# FLYTE-v2.net
KiCad netlist of a schematic drawn in EAGLE
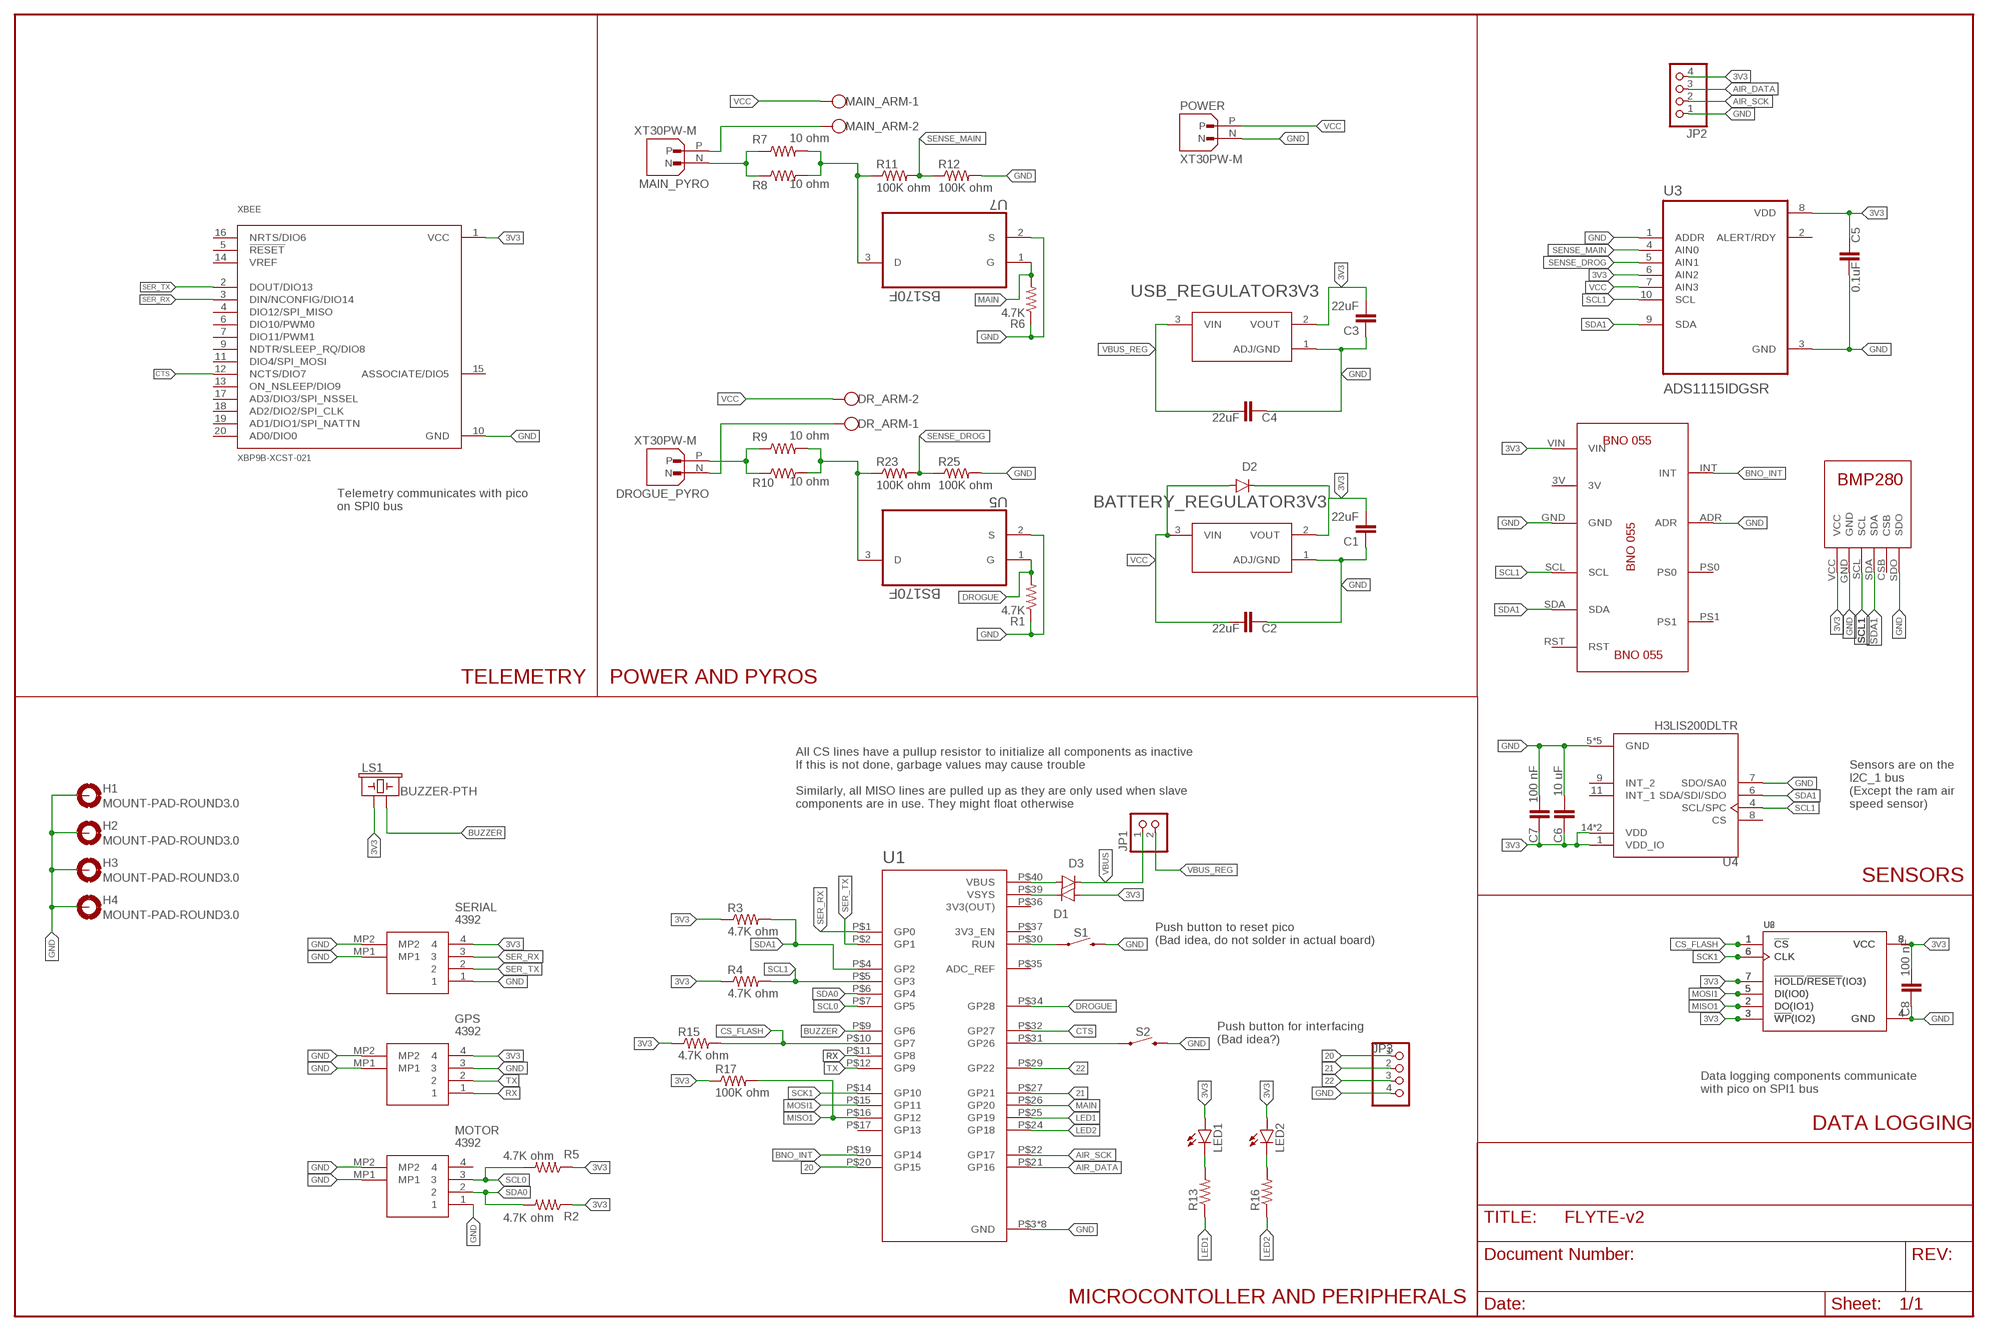
[diagram p0: schematic, sheet 1]

(export (version "E")
  (design (tool "Eeschema 10.0.6"))
  (components
    (comp (ref "BATTERY_REGULATOR3V3")
      (value "AMS1117-3.3")
      (footprint "eagle-import:SOT229P700X180-4N")
      (fields (field (name "MF") "Advanced Monolithic Systems"))
      (libsource (lib "eagle-import") (part "AMS1117-3.3"))
    )
    (comp (ref "C1")
      (value "22uF")
      (footprint "eagle-import:0805")
      (libsource (lib "eagle-import") (part "22UF-0805-6.3V-20%"))
    )
    (comp (ref "C2")
      (value "22uF")
      (footprint "eagle-import:0805")
      (libsource (lib "eagle-import") (part "22UF-0805-6.3V-20%"))
    )
    (comp (ref "C3")
      (value "22uF")
      (footprint "eagle-import:0805")
      (libsource (lib "eagle-import") (part "22UF-0805-6.3V-20%"))
    )
    (comp (ref "C4")
      (value "22uF")
      (footprint "eagle-import:0805")
      (libsource (lib "eagle-import") (part "22UF-0805-6.3V-20%"))
    )
    (comp (ref "C5")
      (value "0.1uF")
      (footprint "eagle-import:0805")
      (libsource (lib "eagle-import") (part "22UF-0805-6.3V-20%"))
    )
    (comp (ref "C6")
      (value "10 uF")
      (footprint "eagle-import:0805")
      (libsource (lib "eagle-import") (part "22UF-0805-6.3V-20%"))
    )
    (comp (ref "C7")
      (value "100 nF")
      (footprint "eagle-import:0805")
      (libsource (lib "eagle-import") (part "22UF-0805-6.3V-20%"))
    )
    (comp (ref "C8")
      (value "100 nF")
      (footprint "eagle-import:0805")
      (libsource (lib "eagle-import") (part "22UF-0805-6.3V-20%"))
    )
    (comp (ref "D1")
      (value "1N4004")
      (footprint "eagle-import:DO41-10")
      (libsource (lib "eagle-import") (part "1N4004"))
    )
    (comp (ref "D2")
      (value "1N4004")
      (footprint "eagle-import:DO41-10")
      (libsource (lib "eagle-import") (part "1N4004"))
    )
    (comp (ref "D3")
      (value "1N4004")
      (footprint "eagle-import:DO41-10")
      (libsource (lib "eagle-import") (part "1N4004"))
    )
    (comp (ref "DROGUE_PYRO")
      (value "XT30PW-M")
      (footprint "eagle-import:AMASS_XT30PW-M")
      (fields (field (name "MF") "AMASS"))
      (libsource (lib "eagle-import") (part "XT30PW-M"))
    )
    (comp (ref "DR_ARM")
      (value "W237-102")
      (footprint "eagle-import:W237-102")
      (fields (field (name "MPN") "237-102"))
      (libsource (lib "eagle-import") (part "W237-102"))
    )
    (comp (ref "GPS")
      (value "4392")
      (footprint "eagle-import:4392")
      (fields (field (name "MOUSER_PART_NUMBER") "485-4392"))
      (libsource (lib "eagle-import") (part "4392"))
    )
    (comp (ref "H1")
      (value "MOUNT-PAD-ROUND3.0")
      (footprint "eagle-import:3,0-PAD")
      (libsource (lib "eagle-import") (part "MOUNT-PAD-ROUND3.0"))
    )
    (comp (ref "H2")
      (value "MOUNT-PAD-ROUND3.0")
      (footprint "eagle-import:3,0-PAD")
      (libsource (lib "eagle-import") (part "MOUNT-PAD-ROUND3.0"))
    )
    (comp (ref "H3")
      (value "MOUNT-PAD-ROUND3.0")
      (footprint "eagle-import:3,0-PAD")
      (libsource (lib "eagle-import") (part "MOUNT-PAD-ROUND3.0"))
    )
    (comp (ref "H4")
      (value "MOUNT-PAD-ROUND3.0")
      (footprint "eagle-import:3,0-PAD")
      (libsource (lib "eagle-import") (part "MOUNT-PAD-ROUND3.0"))
    )
    (comp (ref "JP1")
      (value "PINHD-1X2")
      (footprint "eagle-import:1X02")
      (libsource (lib "eagle-import") (part "PINHD-1X2"))
    )
    (comp (ref "JP2")
      (value "PINHD-1X4")
      (footprint "eagle-import:1X04")
      (libsource (lib "eagle-import") (part "PINHD-1X4"))
    )
    (comp (ref "JP3")
      (value "PINHD-1X4")
      (footprint "eagle-import:1X04")
      (libsource (lib "eagle-import") (part "PINHD-1X4"))
    )
    (comp (ref "LED1")
      (value "LEDCHIPLED_1206")
      (footprint "eagle-import:CHIPLED_1206")
      (libsource (lib "eagle-import") (part "LEDCHIPLED_1206"))
    )
    (comp (ref "LED2")
      (value "LEDCHIPLED_1206")
      (footprint "eagle-import:CHIPLED_1206")
      (libsource (lib "eagle-import") (part "LEDCHIPLED_1206"))
    )
    (comp (ref "LS1")
      (value "BUZZER-PTH")
      (footprint "eagle-import:BUZZER-12MM")
      (libsource (lib "eagle-import") (part "BUZZER-PTH"))
    )
    (comp (ref "MAIN_ARM")
      (value "W237-102")
      (footprint "eagle-import:W237-102")
      (fields (field (name "MPN") "237-102"))
      (libsource (lib "eagle-import") (part "W237-102"))
    )
    (comp (ref "MAIN_PYRO")
      (value "XT30PW-M")
      (footprint "eagle-import:AMASS_XT30PW-M")
      (fields (field (name "MF") "AMASS"))
      (libsource (lib "eagle-import") (part "XT30PW-M"))
    )
    (comp (ref "MOTOR")
      (value "4392")
      (footprint "eagle-import:4392")
      (fields (field (name "MOUSER_PART_NUMBER") "485-4392"))
      (libsource (lib "eagle-import") (part "4392"))
    )
    (comp (ref "POWER")
      (value "XT30PW-M")
      (footprint "eagle-import:AMASS_XT30PW-M")
      (fields (field (name "MF") "AMASS"))
      (libsource (lib "eagle-import") (part "XT30PW-M"))
    )
    (comp (ref "R1")
      (value "4.7K")
      (footprint "eagle-import:R0805")
      (libsource (lib "eagle-import") (part "R-US_R0805"))
    )
    (comp (ref "R2")
      (value "4.7K ohm")
      (footprint "eagle-import:R0805")
      (libsource (lib "eagle-import") (part "R-US_R0805"))
    )
    (comp (ref "R3")
      (value "4.7K ohm")
      (footprint "eagle-import:R0805")
      (libsource (lib "eagle-import") (part "R-US_R0805"))
    )
    (comp (ref "R4")
      (value "4.7K ohm")
      (footprint "eagle-import:R0805")
      (libsource (lib "eagle-import") (part "R-US_R0805"))
    )
    (comp (ref "R5")
      (value "4.7K ohm")
      (footprint "eagle-import:R0805")
      (libsource (lib "eagle-import") (part "R-US_R0805"))
    )
    (comp (ref "R6")
      (value "4.7K")
      (footprint "eagle-import:R0805")
      (libsource (lib "eagle-import") (part "R-US_R0805"))
    )
    (comp (ref "R7")
      (value "10 ohm")
      (footprint "eagle-import:0207_10")
      (libsource (lib "eagle-import") (part "R-US_0207/10"))
    )
    (comp (ref "R8")
      (value "10 ohm")
      (footprint "eagle-import:0207_10")
      (libsource (lib "eagle-import") (part "R-US_0207/10"))
    )
    (comp (ref "R9")
      (value "10 ohm")
      (footprint "eagle-import:0207_10")
      (libsource (lib "eagle-import") (part "R-US_0207/10"))
    )
    (comp (ref "R10")
      (value "10 ohm")
      (footprint "eagle-import:0207_10")
      (libsource (lib "eagle-import") (part "R-US_0207/10"))
    )
    (comp (ref "R11")
      (value "100K ohm")
      (footprint "eagle-import:R0805")
      (libsource (lib "eagle-import") (part "R-US_R0805"))
    )
    (comp (ref "R12")
      (value "100K ohm")
      (footprint "eagle-import:R0805")
      (libsource (lib "eagle-import") (part "R-US_R0805"))
    )
    (comp (ref "R13")
      (value "R-US_R0805")
      (footprint "eagle-import:R0805")
      (libsource (lib "eagle-import") (part "R-US_R0805"))
    )
    (comp (ref "R15")
      (value "4.7K ohm")
      (footprint "eagle-import:R0805")
      (libsource (lib "eagle-import") (part "R-US_R0805"))
    )
    (comp (ref "R16")
      (value "R-US_R0805")
      (footprint "eagle-import:R0805")
      (libsource (lib "eagle-import") (part "R-US_R0805"))
    )
    (comp (ref "R17")
      (value "100K ohm")
      (footprint "eagle-import:R0805")
      (libsource (lib "eagle-import") (part "R-US_R0805"))
    )
    (comp (ref "R23")
      (value "100K ohm")
      (footprint "eagle-import:R0805")
      (libsource (lib "eagle-import") (part "R-US_R0805"))
    )
    (comp (ref "R25")
      (value "100K ohm")
      (footprint "eagle-import:R0805")
      (libsource (lib "eagle-import") (part "R-US_R0805"))
    )
    (comp (ref "S1")
      (value "MOMENTARY-SWITCH-SPST-PTH-6.0MM")
      (footprint "eagle-import:TACTILE_SWITCH_PTH_6.0MM")
      (libsource (lib "eagle-import") (part "MOMENTARY-SWITCH-SPST-PTH-6.0MM"))
    )
    (comp (ref "S2")
      (value "MOMENTARY-SWITCH-SPST-PTH-6.0MM")
      (footprint "eagle-import:TACTILE_SWITCH_PTH_6.0MM")
      (libsource (lib "eagle-import") (part "MOMENTARY-SWITCH-SPST-PTH-6.0MM"))
    )
    (comp (ref "SERIAL")
      (value "4392")
      (footprint "eagle-import:4392")
      (fields (field (name "MOUSER_PART_NUMBER") "485-4392"))
      (libsource (lib "eagle-import") (part "4392"))
    )
    (comp (ref "U$1")
      (value "BMP280")
      (footprint "eagle-import:BMP280")
      (libsource (lib "eagle-import") (part "BMP280"))
    )
    (comp (ref "U$4")
      (value "BNO055")
      (footprint "eagle-import:BNO055")
      (libsource (lib "eagle-import") (part "BNO055"))
    )
    (comp (ref "U1")
      (value "RASPBERRY_PICO-NO_DEBUG")
      (footprint "eagle-import:PICO-PKG-NO_DEBUG")
      (libsource (lib "eagle-import") (part "RASPBERRY_PICO-NO_DEBUG"))
    )
    (comp (ref "U2")
      (value "W25Q32JVSSIQ")
      (footprint "eagle-import:SOIC127P790X216-8N")
      (fields (field (name "MF") "Winbond"))
      (libsource (lib "eagle-import") (part "W25Q32JVSSIQ"))
    )
    (comp (ref "U3")
      (value "ADS1115IDGSR")
      (footprint "eagle-import:SOP50P490X110-10N")
      (fields (field (name "MF") "Texas Instruments"))
      (libsource (lib "eagle-import") (part "ADS1115IDGSR"))
    )
    (comp (ref "U4")
      (value "H3LIS200DLTR")
      (footprint "eagle-import:PQFN50P300X300X100-16N")
      (fields (field (name "MF") "STMicroelectronics"))
      (libsource (lib "eagle-import") (part "H3LIS200DLTR"))
    )
    (comp (ref "U5")
      (value "BS170F")
      (footprint "eagle-import:SOT91P240X120-3N")
      (fields (field (name "MF") "Diodes Inc."))
      (libsource (lib "eagle-import") (part "BS170F"))
    )
    (comp (ref "U6")
      (value "W25Q32JVSSIQ")
      (footprint "eagle-import:SOIC127P790X216-8N")
      (fields (field (name "MF") "Winbond"))
      (libsource (lib "eagle-import") (part "W25Q32JVSSIQ"))
    )
    (comp (ref "U7")
      (value "BS170F")
      (footprint "eagle-import:SOT91P240X120-3N")
      (fields (field (name "MF") "Diodes Inc."))
      (libsource (lib "eagle-import") (part "BS170F"))
    )
    (comp (ref "USB_REGULATOR3V3")
      (value "AMS1117-3.3")
      (footprint "eagle-import:SOT229P700X180-4N")
      (fields (field (name "MF") "Advanced Monolithic Systems"))
      (libsource (lib "eagle-import") (part "AMS1117-3.3"))
    )
    (comp (ref "XBEE")
      (value "XBP9B-XCST-021")
      (footprint "eagle-import:DIP2200W51P200L3294H279Q20P")
      (fields (field (name "MF") "Digi International"))
      (libsource (lib "eagle-import") (part "XBP9B-XCST-021"))
    )
  )
  (nets
    (net (code "1") (name "/3V3(OUT)") (class "Default")
      (node (ref "U1") (pin "P$36") (pinfunction "3V3(OUT)_P$36") (pintype "power_in"))
    )
    (net (code "2") (name "3V3") (class "Default")
      (node (ref "BATTERY_REGULATOR3V3") (pin "2") (pinfunction "VOUT_2") (pintype "output"))
      (node (ref "C1") (pin "2") (pinfunction "2_2") (pintype "passive"))
      (node (ref "C3") (pin "2") (pinfunction "2_2") (pintype "passive"))
      (node (ref "C5") (pin "1") (pinfunction "1_1") (pintype "passive"))
      (node (ref "C6") (pin "1") (pinfunction "1_1") (pintype "passive"))
      (node (ref "C7") (pin "1") (pinfunction "1_1") (pintype "passive"))
      (node (ref "C8") (pin "2") (pinfunction "2_2") (pintype "passive"))
      (node (ref "D1") (pin "A") (pinfunction "A_A") (pintype "passive"))
      (node (ref "D2") (pin "C") (pinfunction "C_C") (pintype "passive"))
      (node (ref "GPS") (pin "4") (pinfunction "4_4") (pintype "bidirectional"))
      (node (ref "JP2") (pin "4") (pinfunction "4_4") (pintype "passive"))
      (node (ref "LED1") (pin "A") (pinfunction "A_A") (pintype "passive"))
      (node (ref "LED2") (pin "A") (pinfunction "A_A") (pintype "passive"))
      (node (ref "LS1") (pin "+") (pinfunction "1_+") (pintype "passive"))
      (node (ref "R15") (pin "1") (pinfunction "1_1") (pintype "passive"))
      (node (ref "R17") (pin "1") (pinfunction "1_1") (pintype "passive"))
      (node (ref "R2") (pin "1") (pinfunction "1_1") (pintype "passive"))
      (node (ref "R3") (pin "1") (pinfunction "1_1") (pintype "passive"))
      (node (ref "R4") (pin "1") (pinfunction "1_1") (pintype "passive"))
      (node (ref "R5") (pin "1") (pinfunction "1_1") (pintype "passive"))
      (node (ref "SERIAL") (pin "4") (pinfunction "4_4") (pintype "bidirectional"))
      (node (ref "U$1") (pin "VCC") (pinfunction "VCC_VCC") (pintype "bidirectional"))
      (node (ref "U$4") (pin "VIN") (pinfunction "VIN_VIN") (pintype "bidirectional"))
      (node (ref "U2") (pin "3") (pinfunction "~{WP}(IO2)_3") (pintype "bidirectional"))
      (node (ref "U2") (pin "7") (pinfunction "~{HOLD}/~{RESET}(IO3)_7") (pintype "bidirectional"))
      (node (ref "U2") (pin "8") (pinfunction "VCC_8") (pintype "power_in"))
      (node (ref "U3") (pin "6") (pinfunction "AIN2_6") (pintype "input"))
      (node (ref "U3") (pin "8") (pinfunction "VDD_8") (pintype "power_in"))
      (node (ref "U4") (pin "1") (pinfunction "VDD_IO_1") (pintype "power_in"))
      (node (ref "U4") (pin "14") (pinfunction "VDD_14") (pintype "power_in"))
      (node (ref "U4") (pin "15") (pinfunction "VDD_15") (pintype "power_in"))
      (node (ref "U6") (pin "3") (pinfunction "~{WP}(IO2)_3") (pintype "bidirectional"))
      (node (ref "U6") (pin "7") (pinfunction "~{HOLD}/~{RESET}(IO3)_7") (pintype "bidirectional"))
      (node (ref "U6") (pin "8") (pinfunction "VCC_8") (pintype "power_in"))
      (node (ref "USB_REGULATOR3V3") (pin "2") (pinfunction "VOUT_2") (pintype "output"))
      (node (ref "XBEE") (pin "1") (pinfunction "VCC_1") (pintype "power_in"))
    )
    (net (code "3") (name "20") (class "Default")
      (node (ref "JP3") (pin "1") (pinfunction "1_1") (pintype "passive"))
      (node (ref "U1") (pin "P$20") (pinfunction "GP15_P$20") (pintype "bidirectional"))
    )
    (net (code "4") (name "21") (class "Default")
      (node (ref "JP3") (pin "2") (pinfunction "2_2") (pintype "passive"))
      (node (ref "U1") (pin "P$27") (pinfunction "GP21_P$27") (pintype "bidirectional"))
    )
    (net (code "5") (name "22") (class "Default")
      (node (ref "JP3") (pin "3") (pinfunction "3_3") (pintype "passive"))
      (node (ref "U1") (pin "P$29") (pinfunction "GP22_P$29") (pintype "bidirectional"))
    )
    (net (code "6") (name "AIR_DATA") (class "Default")
      (node (ref "JP2") (pin "3") (pinfunction "3_3") (pintype "passive"))
      (node (ref "U1") (pin "P$21") (pinfunction "GP16_P$21") (pintype "bidirectional"))
    )
    (net (code "7") (name "AIR_SCK") (class "Default")
      (node (ref "JP2") (pin "2") (pinfunction "2_2") (pintype "passive"))
      (node (ref "U1") (pin "P$22") (pinfunction "GP17_P$22") (pintype "bidirectional"))
    )
    (net (code "8") (name "BNO_INT") (class "Default")
      (node (ref "U$4") (pin "INT") (pinfunction "INT_INT") (pintype "bidirectional"))
      (node (ref "U1") (pin "P$19") (pinfunction "GP14_P$19") (pintype "bidirectional"))
    )
    (net (code "9") (name "BUZZER") (class "Default")
      (node (ref "LS1") (pin "-") (pinfunction "2_-") (pintype "passive"))
      (node (ref "U1") (pin "P$9") (pinfunction "GP6_P$9") (pintype "bidirectional"))
    )
    (net (code "10") (name "CS_FLASH") (class "Default")
      (node (ref "R15") (pin "2") (pinfunction "2_2") (pintype "passive"))
      (node (ref "U1") (pin "P$10") (pinfunction "GP7_P$10") (pintype "bidirectional"))
      (node (ref "U2") (pin "1") (pinfunction "~{CS}_1") (pintype "input"))
      (node (ref "U6") (pin "1") (pinfunction "~{CS}_1") (pintype "input"))
    )
    (net (code "11") (name "CTS") (class "Default")
      (node (ref "U1") (pin "P$32") (pinfunction "GP27_P$32") (pintype "bidirectional"))
      (node (ref "XBEE") (pin "12") (pinfunction "NCTS/DIO7_12") (pintype "bidirectional"))
    )
    (net (code "12") (name "DROGUE") (class "Default")
      (node (ref "R1") (pin "2") (pinfunction "2_2") (pintype "passive"))
      (node (ref "U1") (pin "P$34") (pinfunction "GP28_P$34") (pintype "bidirectional"))
      (node (ref "U5") (pin "1") (pinfunction "G_1") (pintype "passive"))
    )
    (net (code "13") (name "GND") (class "Default")
      (node (ref "BATTERY_REGULATOR3V3") (pin "1") (pinfunction "ADJ/GND_1") (pintype "power_in"))
      (node (ref "C1") (pin "1") (pinfunction "1_1") (pintype "passive"))
      (node (ref "C2") (pin "1") (pinfunction "1_1") (pintype "passive"))
      (node (ref "C3") (pin "1") (pinfunction "1_1") (pintype "passive"))
      (node (ref "C4") (pin "1") (pinfunction "1_1") (pintype "passive"))
      (node (ref "C5") (pin "2") (pinfunction "2_2") (pintype "passive"))
      (node (ref "C6") (pin "2") (pinfunction "2_2") (pintype "passive"))
      (node (ref "C7") (pin "2") (pinfunction "2_2") (pintype "passive"))
      (node (ref "C8") (pin "1") (pinfunction "1_1") (pintype "passive"))
      (node (ref "GPS") (pin "3") (pinfunction "3_3") (pintype "bidirectional"))
      (node (ref "GPS") (pin "MP1") (pinfunction "MP1_MP1") (pintype "bidirectional"))
      (node (ref "GPS") (pin "MP2") (pinfunction "MP2_MP2") (pintype "bidirectional"))
      (node (ref "H1") (pin "B3,0") (pinfunction "MOUNT_B3,0") (pintype "passive"))
      (node (ref "H2") (pin "B3,0") (pinfunction "MOUNT_B3,0") (pintype "passive"))
      (node (ref "H3") (pin "B3,0") (pinfunction "MOUNT_B3,0") (pintype "passive"))
      (node (ref "H4") (pin "B3,0") (pinfunction "MOUNT_B3,0") (pintype "passive"))
      (node (ref "JP2") (pin "1") (pinfunction "1_1") (pintype "passive"))
      (node (ref "JP3") (pin "4") (pinfunction "4_4") (pintype "passive"))
      (node (ref "MOTOR") (pin "1") (pinfunction "1_1") (pintype "bidirectional"))
      (node (ref "MOTOR") (pin "MP1") (pinfunction "MP1_MP1") (pintype "bidirectional"))
      (node (ref "MOTOR") (pin "MP2") (pinfunction "MP2_MP2") (pintype "bidirectional"))
      (node (ref "POWER") (pin "N") (pinfunction "N_N") (pintype "power_in"))
      (node (ref "R1") (pin "1") (pinfunction "1_1") (pintype "passive"))
      (node (ref "R12") (pin "2") (pinfunction "2_2") (pintype "passive"))
      (node (ref "R25") (pin "2") (pinfunction "2_2") (pintype "passive"))
      (node (ref "R6") (pin "1") (pinfunction "1_1") (pintype "passive"))
      (node (ref "S1") (pin "3") (pinfunction "2_3") (pintype "passive"))
      (node (ref "S2") (pin "3") (pinfunction "2_3") (pintype "passive"))
      (node (ref "SERIAL") (pin "1") (pinfunction "1_1") (pintype "bidirectional"))
      (node (ref "SERIAL") (pin "MP1") (pinfunction "MP1_MP1") (pintype "bidirectional"))
      (node (ref "SERIAL") (pin "MP2") (pinfunction "MP2_MP2") (pintype "bidirectional"))
      (node (ref "U$1") (pin "GND") (pinfunction "GND_GND") (pintype "bidirectional"))
      (node (ref "U$1") (pin "SDO") (pinfunction "SDO_SDO") (pintype "bidirectional"))
      (node (ref "U$4") (pin "ADR") (pinfunction "ADR_ADR") (pintype "bidirectional"))
      (node (ref "U$4") (pin "GND") (pinfunction "GND_GND") (pintype "bidirectional"))
      (node (ref "U1") (pin "P$13") (pinfunction "GND_P$13") (pintype "power_in"))
      (node (ref "U1") (pin "P$18") (pinfunction "GND_P$18") (pintype "power_in"))
      (node (ref "U1") (pin "P$23") (pinfunction "GND_P$23") (pintype "power_in"))
      (node (ref "U1") (pin "P$28") (pinfunction "GND_P$28") (pintype "power_in"))
      (node (ref "U1") (pin "P$3") (pinfunction "GND_P$3") (pintype "power_in"))
      (node (ref "U1") (pin "P$33") (pinfunction "GND_P$33") (pintype "power_in"))
      (node (ref "U1") (pin "P$38") (pinfunction "GND_P$38") (pintype "power_in"))
      (node (ref "U1") (pin "P$8") (pinfunction "GND_P$8") (pintype "power_in"))
      (node (ref "U2") (pin "4") (pinfunction "GND_4") (pintype "power_in"))
      (node (ref "U3") (pin "1") (pinfunction "ADDR_1") (pintype "input"))
      (node (ref "U3") (pin "3") (pinfunction "GND_3") (pintype "power_in"))
      (node (ref "U4") (pin "10") (pinfunction "GND_10") (pintype "power_in"))
      (node (ref "U4") (pin "12") (pinfunction "GND_12") (pintype "power_in"))
      (node (ref "U4") (pin "13") (pinfunction "GND_13") (pintype "power_in"))
      (node (ref "U4") (pin "16") (pinfunction "GND_16") (pintype "power_in"))
      (node (ref "U4") (pin "5") (pinfunction "GND_5") (pintype "power_in"))
      (node (ref "U4") (pin "7") (pinfunction "SDO/SA0_7") (pintype "output"))
      (node (ref "U5") (pin "2") (pinfunction "S_2") (pintype "passive"))
      (node (ref "U6") (pin "4") (pinfunction "GND_4") (pintype "power_in"))
      (node (ref "U7") (pin "2") (pinfunction "S_2") (pintype "passive"))
      (node (ref "USB_REGULATOR3V3") (pin "1") (pinfunction "ADJ/GND_1") (pintype "power_in"))
      (node (ref "XBEE") (pin "10") (pinfunction "GND_10") (pintype "power_in"))
    )
    (net (code "14") (name "LED1") (class "Default")
      (node (ref "R13") (pin "1") (pinfunction "1_1") (pintype "passive"))
      (node (ref "U1") (pin "P$25") (pinfunction "GP19_P$25") (pintype "bidirectional"))
    )
    (net (code "15") (name "LED2") (class "Default")
      (node (ref "R16") (pin "1") (pinfunction "1_1") (pintype "passive"))
      (node (ref "U1") (pin "P$24") (pinfunction "GP18_P$24") (pintype "bidirectional"))
    )
    (net (code "16") (name "MAIN") (class "Default")
      (node (ref "R6") (pin "2") (pinfunction "2_2") (pintype "passive"))
      (node (ref "U1") (pin "P$26") (pinfunction "GP20_P$26") (pintype "bidirectional"))
      (node (ref "U7") (pin "1") (pinfunction "G_1") (pintype "passive"))
    )
    (net (code "17") (name "MISO1") (class "Default")
      (node (ref "R17") (pin "2") (pinfunction "2_2") (pintype "passive"))
      (node (ref "U1") (pin "P$16") (pinfunction "GP12_P$16") (pintype "bidirectional"))
      (node (ref "U2") (pin "2") (pinfunction "DO(IO1)_2") (pintype "bidirectional"))
      (node (ref "U6") (pin "2") (pinfunction "DO(IO1)_2") (pintype "bidirectional"))
    )
    (net (code "18") (name "MOSI1") (class "Default")
      (node (ref "U1") (pin "P$15") (pinfunction "GP11_P$15") (pintype "bidirectional"))
      (node (ref "U2") (pin "5") (pinfunction "DI(IO0)_5") (pintype "bidirectional"))
      (node (ref "U6") (pin "5") (pinfunction "DI(IO0)_5") (pintype "bidirectional"))
    )
    (net (code "19") (name "Net-(DROGUE_PYRO-PadP)") (class "Default")
      (node (ref "DROGUE_PYRO") (pin "P") (pinfunction "P_P") (pintype "power_in"))
      (node (ref "R10") (pin "1") (pinfunction "1_1") (pintype "passive"))
      (node (ref "R9") (pin "1") (pinfunction "1_1") (pintype "passive"))
    )
    (net (code "20") (name "Net-(DR_ARMA-KL)") (class "Default")
      (node (ref "DROGUE_PYRO") (pin "N") (pinfunction "N_N") (pintype "power_in"))
      (node (ref "DR_ARM") (pin "1") (pinfunction "KL_1") (pintype "passive"))
    )
    (net (code "21") (name "Net-(LED1-PadC)") (class "Default")
      (node (ref "LED1") (pin "C") (pinfunction "C_C") (pintype "passive"))
      (node (ref "R13") (pin "2") (pinfunction "2_2") (pintype "passive"))
    )
    (net (code "22") (name "Net-(LED2-PadC)") (class "Default")
      (node (ref "LED2") (pin "C") (pinfunction "C_C") (pintype "passive"))
      (node (ref "R16") (pin "2") (pinfunction "2_2") (pintype "passive"))
    )
    (net (code "23") (name "Net-(MAIN_ARMB-KL)") (class "Default")
      (node (ref "MAIN_ARM") (pin "2") (pinfunction "KL_2") (pintype "passive"))
      (node (ref "MAIN_PYRO") (pin "P") (pinfunction "P_P") (pintype "power_in"))
    )
    (net (code "24") (name "Net-(MAIN_PYRO-PadN)") (class "Default")
      (node (ref "MAIN_PYRO") (pin "N") (pinfunction "N_N") (pintype "power_in"))
      (node (ref "R7") (pin "1") (pinfunction "1_1") (pintype "passive"))
      (node (ref "R8") (pin "1") (pinfunction "1_1") (pintype "passive"))
    )
    (net (code "25") (name "Net-(U1-GP26)") (class "Default")
      (node (ref "S2") (pin "1") (pinfunction "1_1") (pintype "passive"))
      (node (ref "U1") (pin "P$31") (pinfunction "GP26_P$31") (pintype "bidirectional"))
    )
    (net (code "26") (name "Net-(U1-RUN)") (class "Default")
      (node (ref "S1") (pin "1") (pinfunction "1_1") (pintype "passive"))
      (node (ref "U1") (pin "P$30") (pinfunction "RUN_P$30") (pintype "input"))
    )
    (net (code "27") (name "Net-(U1-VBUS)") (class "Default")
      (node (ref "D3") (pin "A") (pinfunction "A_A") (pintype "passive"))
      (node (ref "U1") (pin "P$40") (pinfunction "VBUS_P$40") (pintype "power_in"))
    )
    (net (code "28") (name "Net-(U1-VSYS)") (class "Default")
      (node (ref "D1") (pin "C") (pinfunction "C_C") (pintype "passive"))
      (node (ref "U1") (pin "P$39") (pinfunction "VSYS_P$39") (pintype "power_in"))
    )
    (net (code "29") (name "Net-(U5-D)") (class "Default")
      (node (ref "R10") (pin "2") (pinfunction "2_2") (pintype "passive"))
      (node (ref "R23") (pin "1") (pinfunction "1_1") (pintype "passive"))
      (node (ref "R9") (pin "2") (pinfunction "2_2") (pintype "passive"))
      (node (ref "U5") (pin "3") (pinfunction "D_3") (pintype "passive"))
    )
    (net (code "30") (name "Net-(U7-D)") (class "Default")
      (node (ref "R11") (pin "1") (pinfunction "1_1") (pintype "passive"))
      (node (ref "R7") (pin "2") (pinfunction "2_2") (pintype "passive"))
      (node (ref "R8") (pin "2") (pinfunction "2_2") (pintype "passive"))
      (node (ref "U7") (pin "3") (pinfunction "D_3") (pintype "passive"))
    )
    (net (code "31") (name "RX") (class "Default")
      (node (ref "GPS") (pin "1") (pinfunction "1_1") (pintype "bidirectional"))
      (node (ref "U1") (pin "P$11") (pinfunction "GP8_P$11") (pintype "bidirectional"))
    )
    (net (code "32") (name "SCK1") (class "Default")
      (node (ref "U1") (pin "P$14") (pinfunction "GP10_P$14") (pintype "bidirectional"))
      (node (ref "U2") (pin "6") (pinfunction "CLK_6") (pintype "input"))
      (node (ref "U6") (pin "6") (pinfunction "CLK_6") (pintype "input"))
    )
    (net (code "33") (name "SCL0") (class "Default")
      (node (ref "MOTOR") (pin "3") (pinfunction "3_3") (pintype "bidirectional"))
      (node (ref "R5") (pin "2") (pinfunction "2_2") (pintype "passive"))
      (node (ref "U1") (pin "P$7") (pinfunction "GP5_P$7") (pintype "bidirectional"))
    )
    (net (code "34") (name "SCL1") (class "Default")
      (node (ref "R4") (pin "2") (pinfunction "2_2") (pintype "passive"))
      (node (ref "U$1") (pin "SCL") (pinfunction "SCL_SCL") (pintype "bidirectional"))
      (node (ref "U$4") (pin "SCL") (pinfunction "SCL_SCL") (pintype "bidirectional"))
      (node (ref "U1") (pin "P$5") (pinfunction "GP3_P$5") (pintype "bidirectional"))
      (node (ref "U3") (pin "10") (pinfunction "SCL_10") (pintype "input"))
      (node (ref "U4") (pin "4") (pinfunction "SCL/SPC_4") (pintype "input"))
    )
    (net (code "35") (name "SDA0") (class "Default")
      (node (ref "MOTOR") (pin "2") (pinfunction "2_2") (pintype "bidirectional"))
      (node (ref "R2") (pin "2") (pinfunction "2_2") (pintype "passive"))
      (node (ref "U1") (pin "P$6") (pinfunction "GP4_P$6") (pintype "bidirectional"))
    )
    (net (code "36") (name "SDA1") (class "Default")
      (node (ref "R3") (pin "2") (pinfunction "2_2") (pintype "passive"))
      (node (ref "U$1") (pin "SDA") (pinfunction "SDA_SDA") (pintype "bidirectional"))
      (node (ref "U$4") (pin "SDA") (pinfunction "SDA_SDA") (pintype "bidirectional"))
      (node (ref "U1") (pin "P$4") (pinfunction "GP2_P$4") (pintype "bidirectional"))
      (node (ref "U3") (pin "9") (pinfunction "SDA_9") (pintype "bidirectional"))
      (node (ref "U4") (pin "6") (pinfunction "SDA/SDI/SDO_6") (pintype "bidirectional"))
    )
    (net (code "37") (name "SENSE_DROG") (class "Default")
      (node (ref "R23") (pin "2") (pinfunction "2_2") (pintype "passive"))
      (node (ref "R25") (pin "1") (pinfunction "1_1") (pintype "passive"))
      (node (ref "U3") (pin "5") (pinfunction "AIN1_5") (pintype "input"))
    )
    (net (code "38") (name "SENSE_MAIN") (class "Default")
      (node (ref "R11") (pin "2") (pinfunction "2_2") (pintype "passive"))
      (node (ref "R12") (pin "1") (pinfunction "1_1") (pintype "passive"))
      (node (ref "U3") (pin "4") (pinfunction "AIN0_4") (pintype "input"))
    )
    (net (code "39") (name "SER_RX") (class "Default")
      (node (ref "SERIAL") (pin "3") (pinfunction "3_3") (pintype "bidirectional"))
      (node (ref "U1") (pin "P$1") (pinfunction "GP0_P$1") (pintype "bidirectional"))
      (node (ref "XBEE") (pin "3") (pinfunction "DIN/NCONFIG/DIO14_3") (pintype "bidirectional"))
    )
    (net (code "40") (name "SER_TX") (class "Default")
      (node (ref "SERIAL") (pin "2") (pinfunction "2_2") (pintype "bidirectional"))
      (node (ref "U1") (pin "P$2") (pinfunction "GP1_P$2") (pintype "bidirectional"))
      (node (ref "XBEE") (pin "2") (pinfunction "DOUT/DIO13_2") (pintype "bidirectional"))
    )
    (net (code "41") (name "TX") (class "Default")
      (node (ref "GPS") (pin "2") (pinfunction "2_2") (pintype "bidirectional"))
      (node (ref "U1") (pin "P$12") (pinfunction "GP9_P$12") (pintype "bidirectional"))
    )
    (net (code "42") (name "VBUS") (class "Default")
      (node (ref "D3") (pin "C") (pinfunction "C_C") (pintype "passive"))
      (node (ref "JP1") (pin "1") (pinfunction "1_1") (pintype "passive"))
    )
    (net (code "43") (name "VBUS_REG") (class "Default")
      (node (ref "C4") (pin "2") (pinfunction "2_2") (pintype "passive"))
      (node (ref "JP1") (pin "2") (pinfunction "2_2") (pintype "passive"))
      (node (ref "USB_REGULATOR3V3") (pin "3") (pinfunction "VIN_3") (pintype "input"))
    )
    (net (code "44") (name "VCC") (class "Default")
      (node (ref "BATTERY_REGULATOR3V3") (pin "3") (pinfunction "VIN_3") (pintype "input"))
      (node (ref "C2") (pin "2") (pinfunction "2_2") (pintype "passive"))
      (node (ref "D2") (pin "A") (pinfunction "A_A") (pintype "passive"))
      (node (ref "DR_ARM") (pin "2") (pinfunction "KL_2") (pintype "passive"))
      (node (ref "MAIN_ARM") (pin "1") (pinfunction "KL_1") (pintype "passive"))
      (node (ref "POWER") (pin "P") (pinfunction "P_P") (pintype "power_in"))
      (node (ref "U3") (pin "7") (pinfunction "AIN3_7") (pintype "input"))
    )
    (net (code "45") (name "unconnected-(MOTOR-Pad4)") (class "Default")
      (node (ref "MOTOR") (pin "4") (pinfunction "4_4") (pintype "bidirectional"))
    )
    (net (code "46") (name "unconnected-(U$1-PadCSB)") (class "Default")
      (node (ref "U$1") (pin "CSB") (pinfunction "CSB_CSB") (pintype "bidirectional"))
    )
    (net (code "47") (name "unconnected-(U$4-Pad3V)") (class "Default")
      (node (ref "U$4") (pin "3V") (pinfunction "3V_3V") (pintype "bidirectional"))
    )
    (net (code "48") (name "unconnected-(U$4-PadPS0)") (class "Default")
      (node (ref "U$4") (pin "PS0") (pinfunction "PS0_PS0") (pintype "bidirectional"))
    )
    (net (code "49") (name "unconnected-(U$4-PadPS1)") (class "Default")
      (node (ref "U$4") (pin "PS1") (pinfunction "PS1_PS1") (pintype "bidirectional"))
    )
    (net (code "50") (name "unconnected-(U$4-PadRST)") (class "Default")
      (node (ref "U$4") (pin "RST") (pinfunction "RST_RST") (pintype "bidirectional"))
    )
    (net (code "51") (name "unconnected-(U1-3V3_EN-PadP$37)") (class "Default")
      (node (ref "U1") (pin "P$37") (pinfunction "3V3_EN_P$37") (pintype "input"))
    )
    (net (code "52") (name "unconnected-(U1-ADC_REF-PadP$35)") (class "Default")
      (node (ref "U1") (pin "P$35") (pinfunction "ADC_REF_P$35") (pintype "input"))
    )
    (net (code "53") (name "unconnected-(U1-GP13-PadP$17)") (class "Default")
      (node (ref "U1") (pin "P$17") (pinfunction "GP13_P$17") (pintype "bidirectional"))
    )
    (net (code "54") (name "unconnected-(U3-ALERT{slash}RDY-Pad2)") (class "Default")
      (node (ref "U3") (pin "2") (pinfunction "ALERT/RDY_2") (pintype "output"))
    )
    (net (code "55") (name "unconnected-(U4-CS-Pad8)") (class "Default")
      (node (ref "U4") (pin "8") (pinfunction "CS_8") (pintype "input"))
    )
    (net (code "56") (name "unconnected-(U4-INT_1-Pad11)") (class "Default")
      (node (ref "U4") (pin "11") (pinfunction "INT_1_11") (pintype "output"))
    )
    (net (code "57") (name "unconnected-(U4-INT_2-Pad9)") (class "Default")
      (node (ref "U4") (pin "9") (pinfunction "INT_2_9") (pintype "output"))
    )
    (net (code "58") (name "unconnected-(XBEE-AD0{slash}DIO0-Pad20)") (class "Default")
      (node (ref "XBEE") (pin "20") (pinfunction "AD0/DIO0_20") (pintype "bidirectional"))
    )
    (net (code "59") (name "unconnected-(XBEE-AD1{slash}DIO1{slash}SPI_NATTN-Pad19)") (class "Default")
      (node (ref "XBEE") (pin "19") (pinfunction "AD1/DIO1/SPI_NATTN_19") (pintype "bidirectional"))
    )
    (net (code "60") (name "unconnected-(XBEE-AD2{slash}DIO2{slash}SPI_CLK-Pad18)") (class "Default")
      (node (ref "XBEE") (pin "18") (pinfunction "AD2/DIO2/SPI_CLK_18") (pintype "bidirectional"))
    )
    (net (code "61") (name "unconnected-(XBEE-AD3{slash}DIO3{slash}SPI_NSSEL-Pad17)") (class "Default")
      (node (ref "XBEE") (pin "17") (pinfunction "AD3/DIO3/SPI_NSSEL_17") (pintype "bidirectional"))
    )
    (net (code "62") (name "unconnected-(XBEE-ASSOCIATE{slash}DIO5-Pad15)") (class "Default")
      (node (ref "XBEE") (pin "15") (pinfunction "ASSOCIATE/DIO5_15") (pintype "output"))
    )
    (net (code "63") (name "unconnected-(XBEE-DIO4{slash}SPI_MOSI-Pad11)") (class "Default")
      (node (ref "XBEE") (pin "11") (pinfunction "DIO4/SPI_MOSI_11") (pintype "bidirectional"))
    )
    (net (code "64") (name "unconnected-(XBEE-DIO10{slash}PWM0-Pad6)") (class "Default")
      (node (ref "XBEE") (pin "6") (pinfunction "DIO10/PWM0_6") (pintype "bidirectional"))
    )
    (net (code "65") (name "unconnected-(XBEE-DIO11{slash}PWM1-Pad7)") (class "Default")
      (node (ref "XBEE") (pin "7") (pinfunction "DIO11/PWM1_7") (pintype "bidirectional"))
    )
    (net (code "66") (name "unconnected-(XBEE-DIO12{slash}SPI_MISO-Pad4)") (class "Default")
      (node (ref "XBEE") (pin "4") (pinfunction "DIO12/SPI_MISO_4") (pintype "bidirectional"))
    )
    (net (code "67") (name "unconnected-(XBEE-NDTR{slash}SLEEP_RQ{slash}DIO8-Pad9)") (class "Default")
      (node (ref "XBEE") (pin "9") (pinfunction "NDTR/SLEEP_RQ/DIO8_9") (pintype "bidirectional"))
    )
    (net (code "68") (name "unconnected-(XBEE-NRTS{slash}DIO6-Pad16)") (class "Default")
      (node (ref "XBEE") (pin "16") (pinfunction "NRTS/DIO6_16") (pintype "input"))
    )
    (net (code "69") (name "unconnected-(XBEE-ON_NSLEEP{slash}DIO9-Pad13)") (class "Default")
      (node (ref "XBEE") (pin "13") (pinfunction "ON_NSLEEP/DIO9_13") (pintype "bidirectional"))
    )
    (net (code "70") (name "unconnected-(XBEE-VREF-Pad14)") (class "Default")
      (node (ref "XBEE") (pin "14") (pinfunction "VREF_14") (pintype "input"))
    )
    (net (code "71") (name "unconnected-(XBEE-~{RESET}-Pad5)") (class "Default")
      (node (ref "XBEE") (pin "5") (pinfunction "~{RESET}_5") (pintype "input"))
    )
  )
)
